# Breakout.net
KiCad netlist of a schematic drawn in Altium Designer
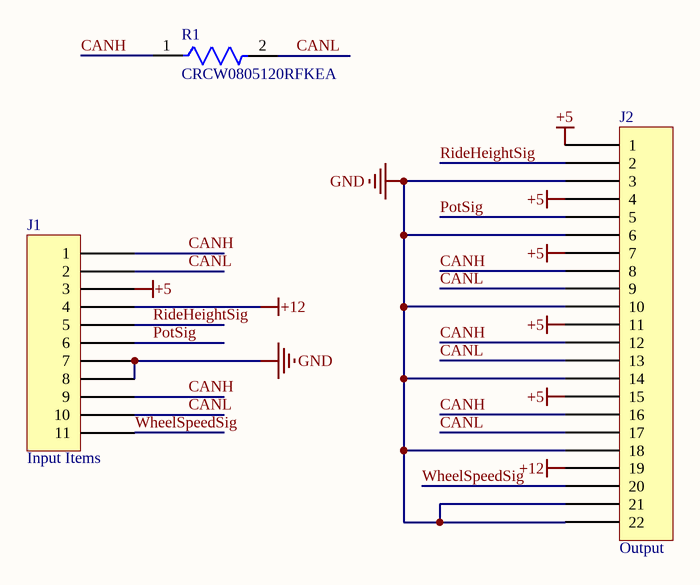
[diagram p0: Breakout.SchDoc]

(export (version "E")
  (design (tool "Eeschema 10.0.6"))
  (components
    (comp (ref "J1") (value "Input Items") (footprint "Input") (libsource (lib "BreakoutLib") (part "Input")))
    (comp (ref "J2") (value "Output") (footprint "Output") (libsource (lib "BreakoutLib") (part "Output")))
    (comp (ref "R1")
      (value "CRCW0805120RFKEA")
      (footprint "FP-CRCW0805-e3-IPC_C")
      (description "RES Thick Film, 120Ω, 1%, 0.125W, 100ppm/°C, 0805")
      (fields (field (name "TOLERANCE") "1%"))
      (libsource (lib "Altium Content Vault") (part "1029c3af85768c4190bb7ad29bc67b5"))
    )
  )
  (nets
    (net (code "1") (name "+5") (class "Default")
      (node (ref "J1") (pin "3") (pinfunction "3_3") (pintype "passive"))
      (node (ref "J2") (pin "1") (pinfunction "1_1") (pintype "passive"))
      (node (ref "J2") (pin "11") (pinfunction "11_11") (pintype "passive"))
      (node (ref "J2") (pin "15") (pinfunction "15_15") (pintype "passive"))
      (node (ref "J2") (pin "4") (pinfunction "4_4") (pintype "passive"))
      (node (ref "J2") (pin "7") (pinfunction "7_7") (pintype "passive"))
    )
    (net (code "2") (name "+12") (class "Default")
      (node (ref "J1") (pin "4") (pinfunction "4_4") (pintype "passive"))
      (node (ref "J2") (pin "19") (pinfunction "19_19") (pintype "passive"))
    )
    (net (code "3") (name "/CANH") (class "Default")
      (node (ref "J1") (pin "1") (pinfunction "1_1") (pintype "passive"))
      (node (ref "J1") (pin "9") (pinfunction "9_9") (pintype "passive"))
      (node (ref "J2") (pin "12") (pinfunction "12_12") (pintype "passive"))
      (node (ref "J2") (pin "16") (pinfunction "16_16") (pintype "passive"))
      (node (ref "J2") (pin "8") (pinfunction "8_8") (pintype "passive"))
      (node (ref "R1") (pin "1") (pinfunction "1_1") (pintype "passive"))
    )
    (net (code "4") (name "/CANL") (class "Default")
      (node (ref "J1") (pin "10") (pinfunction "10_10") (pintype "passive"))
      (node (ref "J1") (pin "2") (pinfunction "2_2") (pintype "passive"))
      (node (ref "J2") (pin "13") (pinfunction "13_13") (pintype "passive"))
      (node (ref "J2") (pin "17") (pinfunction "17_17") (pintype "passive"))
      (node (ref "J2") (pin "9") (pinfunction "9_9") (pintype "passive"))
      (node (ref "R1") (pin "2") (pinfunction "2_2") (pintype "passive"))
    )
    (net (code "5") (name "/PotSig") (class "Default")
      (node (ref "J1") (pin "6") (pinfunction "6_6") (pintype "passive"))
      (node (ref "J2") (pin "5") (pinfunction "5_5") (pintype "passive"))
    )
    (net (code "6") (name "/RideHeightSig") (class "Default")
      (node (ref "J1") (pin "5") (pinfunction "5_5") (pintype "passive"))
      (node (ref "J2") (pin "2") (pinfunction "2_2") (pintype "passive"))
    )
    (net (code "7") (name "/WheelSpeedSig") (class "Default")
      (node (ref "J1") (pin "11") (pinfunction "11_11") (pintype "passive"))
      (node (ref "J2") (pin "20") (pinfunction "20_20") (pintype "passive"))
    )
    (net (code "8") (name "GND") (class "Default")
      (node (ref "J1") (pin "7") (pinfunction "7_7") (pintype "passive"))
      (node (ref "J1") (pin "8") (pinfunction "8_8") (pintype "passive"))
      (node (ref "J2") (pin "10") (pinfunction "10_10") (pintype "passive"))
      (node (ref "J2") (pin "14") (pinfunction "14_14") (pintype "passive"))
      (node (ref "J2") (pin "18") (pinfunction "18_18") (pintype "passive"))
      (node (ref "J2") (pin "21") (pinfunction "21_21") (pintype "passive"))
      (node (ref "J2") (pin "22") (pinfunction "22_22") (pintype "passive"))
      (node (ref "J2") (pin "3") (pinfunction "3_3") (pintype "passive"))
      (node (ref "J2") (pin "6") (pinfunction "6_6") (pintype "passive"))
    )
  )
)
